# JOYSTICK.net
KiCad netlist of a schematic drawn in EAGLE
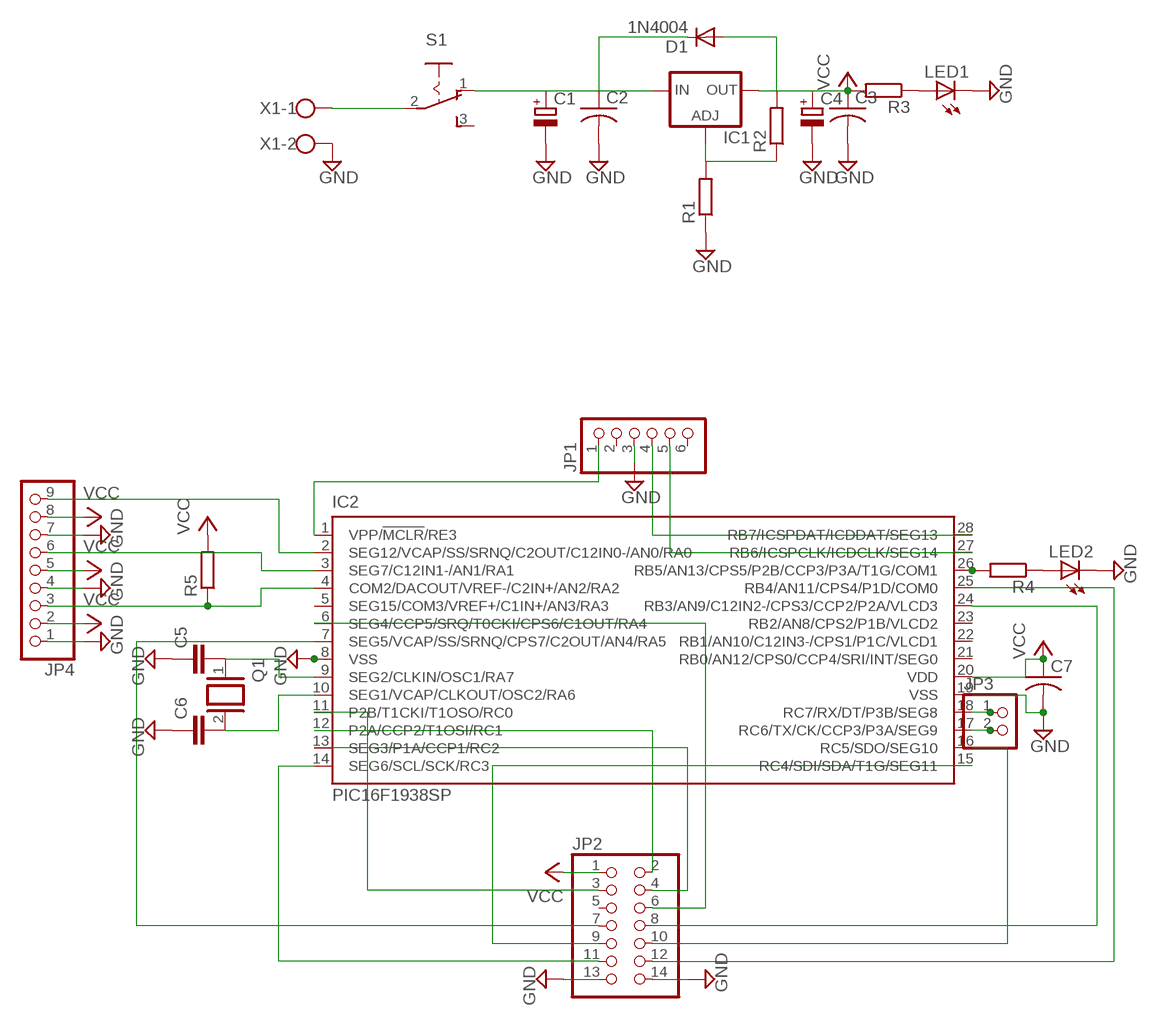
[diagram p0: schematic, sheet 1]

(export (version "E")
  (design (tool "Eeschema 10.0.6"))
  (components
    (comp (ref "C1")
      (value "CPOL-EUE3.5-8")
      (footprint "eagle-import:E3,5-8")
      (libsource (lib "eagle-import") (part "CPOL-EUE3.5-8"))
    )
    (comp (ref "C2")
      (value "C-US050-030X075")
      (footprint "eagle-import:C050-030X075")
      (libsource (lib "eagle-import") (part "C-US050-030X075"))
    )
    (comp (ref "C3")
      (value "C-US050-030X075")
      (footprint "eagle-import:C050-030X075")
      (libsource (lib "eagle-import") (part "C-US050-030X075"))
    )
    (comp (ref "C4")
      (value "CPOL-EUE3.5-8")
      (footprint "eagle-import:E3,5-8")
      (libsource (lib "eagle-import") (part "CPOL-EUE3.5-8"))
    )
    (comp (ref "C5")
      (value "C-EU025-025X050")
      (footprint "eagle-import:C025-025X050")
      (libsource (lib "eagle-import") (part "C-EU025-025X050"))
    )
    (comp (ref "C6")
      (value "C-EU025-025X050")
      (footprint "eagle-import:C025-025X050")
      (libsource (lib "eagle-import") (part "C-EU025-025X050"))
    )
    (comp (ref "C7")
      (value "C-US050-030X075")
      (footprint "eagle-import:C050-030X075")
      (libsource (lib "eagle-import") (part "C-US050-030X075"))
    )
    (comp (ref "D1")
      (value "1N4004")
      (footprint "eagle-import:DO41-10")
      (libsource (lib "eagle-import") (part "1N4004"))
    )
    (comp (ref "IC1")
      (value "LM317TS")
      (footprint "eagle-import:317TS")
      (libsource (lib "eagle-import") (part "LM317TS"))
    )
    (comp (ref "IC2")
      (value "PIC16F1938SP")
      (footprint "eagle-import:DIL28-3")
      (fields (field (name "MPN") "PIC16F1938-I/SP"))
      (libsource (lib "eagle-import") (part "PIC16F19SP38"))
    )
    (comp (ref "JP1")
      (value "PINHD-1X6")
      (footprint "eagle-import:1X06")
      (libsource (lib "eagle-import") (part "PINHD-1X6"))
    )
    (comp (ref "JP2")
      (value "PINHD-2X7")
      (footprint "eagle-import:2X07")
      (libsource (lib "eagle-import") (part "PINHD-2X7"))
    )
    (comp (ref "JP3")
      (value "PINHD-1X2")
      (footprint "eagle-import:1X02")
      (libsource (lib "eagle-import") (part "PINHD-1X2"))
    )
    (comp (ref "JP4")
      (value "PINHD-1X9")
      (footprint "eagle-import:1X09")
      (libsource (lib "eagle-import") (part "PINHD-1X9"))
    )
    (comp (ref "LED1")
      (value "LED5MM")
      (footprint "eagle-import:LED5MM")
      (libsource (lib "eagle-import") (part "LED5MM"))
    )
    (comp (ref "LED2")
      (value "LED5MM")
      (footprint "eagle-import:LED5MM")
      (libsource (lib "eagle-import") (part "LED5MM"))
    )
    (comp (ref "Q1")
      (value "XTAL/S")
      (footprint "eagle-import:QS")
      (libsource (lib "eagle-import") (part "XTAL/S"))
    )
    (comp (ref "R1")
      (value "R-EU_0207/10")
      (footprint "eagle-import:0207_10")
      (libsource (lib "eagle-import") (part "R-EU_0207/10"))
    )
    (comp (ref "R2")
      (value "R-EU_0207/10")
      (footprint "eagle-import:0207_10")
      (libsource (lib "eagle-import") (part "R-EU_0207/10"))
    )
    (comp (ref "R3")
      (value "R-EU_0207/10")
      (footprint "eagle-import:0207_10")
      (libsource (lib "eagle-import") (part "R-EU_0207/10"))
    )
    (comp (ref "R4")
      (value "R-EU_0207/10")
      (footprint "eagle-import:0207_10")
      (libsource (lib "eagle-import") (part "R-EU_0207/10"))
    )
    (comp (ref "R5")
      (value "R-EU_0207/10")
      (footprint "eagle-import:0207_10")
      (libsource (lib "eagle-import") (part "R-EU_0207/10"))
    )
    (comp (ref "S1")
      (value "255SB")
      (footprint "eagle-import:255SB")
      (libsource (lib "eagle-import") (part "255SB"))
    )
    (comp (ref "X1")
      (value "W237-102")
      (footprint "eagle-import:W237-102")
      (fields (field (name "MPN") "237-102"))
      (libsource (lib "eagle-import") (part "W237-102"))
    )
  )
  (nets
    (net (code "1") (name "GND") (class "Default")
      (node (ref "C1") (pin "-") (pinfunction "-_-") (pintype "passive"))
      (node (ref "C2") (pin "2") (pinfunction "2_2") (pintype "passive"))
      (node (ref "C3") (pin "2") (pinfunction "2_2") (pintype "passive"))
      (node (ref "C4") (pin "-") (pinfunction "-_-") (pintype "passive"))
      (node (ref "C5") (pin "1") (pinfunction "1_1") (pintype "passive"))
      (node (ref "C6") (pin "1") (pinfunction "1_1") (pintype "passive"))
      (node (ref "C7") (pin "2") (pinfunction "2_2") (pintype "passive"))
      (node (ref "IC2") (pin "19") (pinfunction "VSS_19") (pintype "power_in"))
      (node (ref "IC2") (pin "8") (pinfunction "VSS_8") (pintype "power_in"))
      (node (ref "JP1") (pin "3") (pinfunction "3_3") (pintype "passive"))
      (node (ref "JP2") (pin "13") (pinfunction "13_13") (pintype "passive"))
      (node (ref "JP2") (pin "14") (pinfunction "14_14") (pintype "passive"))
      (node (ref "JP4") (pin "1") (pinfunction "1_1") (pintype "passive"))
      (node (ref "JP4") (pin "4") (pinfunction "4_4") (pintype "passive"))
      (node (ref "JP4") (pin "7") (pinfunction "7_7") (pintype "passive"))
      (node (ref "LED1") (pin "K") (pinfunction "C_K") (pintype "passive"))
      (node (ref "LED2") (pin "K") (pinfunction "C_K") (pintype "passive"))
      (node (ref "R1") (pin "1") (pinfunction "1_1") (pintype "passive"))
      (node (ref "X1") (pin "2") (pinfunction "KL_2") (pintype "passive"))
    )
    (net (code "2") (name "Net-(IC1-ADJ)") (class "Default")
      (node (ref "IC1") (pin "1") (pinfunction "ADJ_1") (pintype "input"))
      (node (ref "R1") (pin "2") (pinfunction "2_2") (pintype "passive"))
      (node (ref "R2") (pin "1") (pinfunction "1_1") (pintype "passive"))
    )
    (net (code "3") (name "Net-(IC1-IN)") (class "Default")
      (node (ref "C1") (pin "+") (pinfunction "+_+") (pintype "passive"))
      (node (ref "C2") (pin "1") (pinfunction "1_1") (pintype "passive"))
      (node (ref "D1") (pin "C") (pinfunction "C_C") (pintype "passive"))
      (node (ref "IC1") (pin "3") (pinfunction "IN_3") (pintype "input"))
      (node (ref "S1") (pin "1") (pinfunction "O_1") (pintype "passive"))
    )
    (net (code "4") (name "Net-(IC2-COM2{slash}DACOUT{slash}VREF-{slash}C2IN+{slash}AN2{slash}RA2)") (class "Default")
      (node (ref "IC2") (pin "4") (pinfunction "COM2/DACOUT/VREF-/C2IN+/AN2/RA2_4") (pintype "bidirectional"))
      (node (ref "JP4") (pin "3") (pinfunction "3_3") (pintype "passive"))
      (node (ref "R5") (pin "1") (pinfunction "1_1") (pintype "passive"))
    )
    (net (code "5") (name "Net-(IC2-P2A{slash}CCP2{slash}T1OSI{slash}RC1)") (class "Default")
      (node (ref "IC2") (pin "12") (pinfunction "P2A/CCP2/T1OSI/RC1_12") (pintype "bidirectional"))
      (node (ref "JP2") (pin "2") (pinfunction "2_2") (pintype "passive"))
    )
    (net (code "6") (name "Net-(IC2-P2B{slash}T1CKI{slash}T1OSO{slash}RC0)") (class "Default")
      (node (ref "IC2") (pin "11") (pinfunction "P2B/T1CKI/T1OSO/RC0_11") (pintype "bidirectional"))
      (node (ref "JP2") (pin "3") (pinfunction "3_3") (pintype "passive"))
    )
    (net (code "7") (name "Net-(IC2-RB3{slash}AN9{slash}C12IN2-{slash}CPS3{slash}CCP2{slash}P2A{slash}VLCD3)") (class "Default")
      (node (ref "IC2") (pin "24") (pinfunction "RB3/AN9/C12IN2-/CPS3/CCP2/P2A/VLCD3_24") (pintype "bidirectional"))
      (node (ref "JP2") (pin "8") (pinfunction "8_8") (pintype "passive"))
    )
    (net (code "8") (name "Net-(IC2-RB4{slash}AN11{slash}CPS4{slash}P1D{slash}COM0)") (class "Default")
      (node (ref "IC2") (pin "25") (pinfunction "RB4/AN11/CPS4/P1D/COM0_25") (pintype "bidirectional"))
      (node (ref "JP2") (pin "12") (pinfunction "12_12") (pintype "passive"))
    )
    (net (code "9") (name "Net-(IC2-RB5{slash}AN13{slash}CPS5{slash}P2B{slash}CCP3{slash}P3A{slash}T1G{slash}COM1)") (class "Default")
      (node (ref "IC2") (pin "26") (pinfunction "RB5/AN13/CPS5/P2B/CCP3/P3A/T1G/COM1_26") (pintype "bidirectional"))
      (node (ref "R4") (pin "2") (pinfunction "2_2") (pintype "passive"))
    )
    (net (code "10") (name "Net-(IC2-RB6{slash}ICSPCLK{slash}ICDCLK{slash}SEG14)") (class "Default")
      (node (ref "IC2") (pin "27") (pinfunction "RB6/ICSPCLK/ICDCLK/SEG14_27") (pintype "bidirectional"))
      (node (ref "JP1") (pin "5") (pinfunction "5_5") (pintype "passive"))
    )
    (net (code "11") (name "Net-(IC2-RB7{slash}ICSPDAT{slash}ICDDAT{slash}SEG13)") (class "Default")
      (node (ref "IC2") (pin "28") (pinfunction "RB7/ICSPDAT/ICDDAT/SEG13_28") (pintype "bidirectional"))
      (node (ref "JP1") (pin "4") (pinfunction "4_4") (pintype "passive"))
    )
    (net (code "12") (name "Net-(IC2-RC4{slash}SDI{slash}SDA{slash}T1G{slash}SEG11)") (class "Default")
      (node (ref "IC2") (pin "15") (pinfunction "RC4/SDI/SDA/T1G/SEG11_15") (pintype "bidirectional"))
      (node (ref "JP2") (pin "9") (pinfunction "9_9") (pintype "passive"))
    )
    (net (code "13") (name "Net-(IC2-RC5{slash}SDO{slash}SEG10)") (class "Default")
      (node (ref "IC2") (pin "16") (pinfunction "RC5/SDO/SEG10_16") (pintype "bidirectional"))
      (node (ref "JP2") (pin "10") (pinfunction "10_10") (pintype "passive"))
    )
    (net (code "14") (name "Net-(IC2-RC6{slash}TX{slash}CK{slash}CCP3{slash}P3A{slash}SEG9)") (class "Default")
      (node (ref "IC2") (pin "17") (pinfunction "RC6/TX/CK/CCP3/P3A/SEG9_17") (pintype "bidirectional"))
      (node (ref "JP3") (pin "2") (pinfunction "2_2") (pintype "passive"))
    )
    (net (code "15") (name "Net-(IC2-RC7{slash}RX{slash}DT{slash}P3B{slash}SEG8)") (class "Default")
      (node (ref "IC2") (pin "18") (pinfunction "RC7/RX/DT/P3B/SEG8_18") (pintype "bidirectional"))
      (node (ref "JP3") (pin "1") (pinfunction "1_1") (pintype "passive"))
    )
    (net (code "16") (name "Net-(IC2-SEG1{slash}VCAP{slash}CLKOUT{slash}OSC2{slash}RA6)") (class "Default")
      (node (ref "C6") (pin "2") (pinfunction "2_2") (pintype "passive"))
      (node (ref "IC2") (pin "10") (pinfunction "SEG1/VCAP/CLKOUT/OSC2/RA6_10") (pintype "bidirectional"))
      (node (ref "Q1") (pin "2") (pinfunction "2_2") (pintype "passive"))
    )
    (net (code "17") (name "Net-(IC2-SEG2{slash}CLKIN{slash}OSC1{slash}RA7)") (class "Default")
      (node (ref "C5") (pin "2") (pinfunction "2_2") (pintype "passive"))
      (node (ref "IC2") (pin "9") (pinfunction "SEG2/CLKIN/OSC1/RA7_9") (pintype "bidirectional"))
      (node (ref "Q1") (pin "1") (pinfunction "1_1") (pintype "passive"))
    )
    (net (code "18") (name "Net-(IC2-SEG3{slash}P1A{slash}CCP1{slash}RC2)") (class "Default")
      (node (ref "IC2") (pin "13") (pinfunction "SEG3/P1A/CCP1/RC2_13") (pintype "bidirectional"))
      (node (ref "JP2") (pin "4") (pinfunction "4_4") (pintype "passive"))
    )
    (net (code "19") (name "Net-(IC2-SEG4{slash}CCP5{slash}SRQ{slash}T0CKI{slash}CPS6{slash}C1OUT{slash}RA4)") (class "Default")
      (node (ref "IC2") (pin "6") (pinfunction "SEG4/CCP5/SRQ/T0CKI/CPS6/C1OUT/RA4_6") (pintype "bidirectional"))
      (node (ref "JP2") (pin "6") (pinfunction "6_6") (pintype "passive"))
    )
    (net (code "20") (name "Net-(IC2-SEG5{slash}VCAP{slash}SS{slash}SRNQ{slash}CPS7{slash}C2OUT{slash}AN4{slash}RA5)") (class "Default")
      (node (ref "IC2") (pin "7") (pinfunction "SEG5/VCAP/SS/SRNQ/CPS7/C2OUT/AN4/RA5_7") (pintype "bidirectional"))
      (node (ref "JP2") (pin "7") (pinfunction "7_7") (pintype "passive"))
    )
    (net (code "21") (name "Net-(IC2-SEG6{slash}SCL{slash}SCK{slash}RC3)") (class "Default")
      (node (ref "IC2") (pin "14") (pinfunction "SEG6/SCL/SCK/RC3_14") (pintype "bidirectional"))
      (node (ref "JP2") (pin "11") (pinfunction "11_11") (pintype "passive"))
    )
    (net (code "22") (name "Net-(IC2-SEG7{slash}C12IN1-{slash}AN1{slash}RA1)") (class "Default")
      (node (ref "IC2") (pin "3") (pinfunction "SEG7/C12IN1-/AN1/RA1_3") (pintype "bidirectional"))
      (node (ref "JP4") (pin "6") (pinfunction "6_6") (pintype "passive"))
    )
    (net (code "23") (name "Net-(IC2-SEG12{slash}VCAP{slash}SS{slash}SRNQ{slash}C2OUT{slash}C12IN0-{slash}AN0{slash}RA0)") (class "Default")
      (node (ref "IC2") (pin "2") (pinfunction "SEG12/VCAP/SS/SRNQ/C2OUT/C12IN0-/AN0/RA0_2") (pintype "bidirectional"))
      (node (ref "JP4") (pin "9") (pinfunction "9_9") (pintype "passive"))
    )
    (net (code "24") (name "Net-(IC2-VPP{slash}~{MCLR}{slash}RE3)") (class "Default")
      (node (ref "IC2") (pin "1") (pinfunction "VPP/~{MCLR}/RE3_1") (pintype "input"))
      (node (ref "JP1") (pin "1") (pinfunction "1_1") (pintype "passive"))
    )
    (net (code "25") (name "Net-(LED1-PadA)") (class "Default")
      (node (ref "LED1") (pin "A") (pinfunction "A_A") (pintype "passive"))
      (node (ref "R3") (pin "1") (pinfunction "1_1") (pintype "passive"))
    )
    (net (code "26") (name "Net-(LED2-PadA)") (class "Default")
      (node (ref "LED2") (pin "A") (pinfunction "A_A") (pintype "passive"))
      (node (ref "R4") (pin "1") (pinfunction "1_1") (pintype "passive"))
    )
    (net (code "27") (name "Net-(S1-P)") (class "Default")
      (node (ref "S1") (pin "2") (pinfunction "P_2") (pintype "passive"))
      (node (ref "X1") (pin "1") (pinfunction "KL_1") (pintype "passive"))
    )
    (net (code "28") (name "VCC") (class "Default")
      (node (ref "C3") (pin "1") (pinfunction "1_1") (pintype "passive"))
      (node (ref "C4") (pin "+") (pinfunction "+_+") (pintype "passive"))
      (node (ref "C7") (pin "1") (pinfunction "1_1") (pintype "passive"))
      (node (ref "D1") (pin "A") (pinfunction "A_A") (pintype "passive"))
      (node (ref "IC1") (pin "2") (pinfunction "OUT_2") (pintype "passive"))
      (node (ref "IC2") (pin "20") (pinfunction "VDD_20") (pintype "power_in"))
      (node (ref "JP2") (pin "1") (pinfunction "1_1") (pintype "passive"))
      (node (ref "JP4") (pin "2") (pinfunction "2_2") (pintype "passive"))
      (node (ref "JP4") (pin "5") (pinfunction "5_5") (pintype "passive"))
      (node (ref "JP4") (pin "8") (pinfunction "8_8") (pintype "passive"))
      (node (ref "R2") (pin "2") (pinfunction "2_2") (pintype "passive"))
      (node (ref "R3") (pin "2") (pinfunction "2_2") (pintype "passive"))
      (node (ref "R5") (pin "2") (pinfunction "2_2") (pintype "passive"))
    )
    (net (code "29") (name "unconnected-(IC2-RB0{slash}AN12{slash}CPS0{slash}CCP4{slash}SRI{slash}INT{slash}SEG0-Pad21)") (class "Default")
      (node (ref "IC2") (pin "21") (pinfunction "RB0/AN12/CPS0/CCP4/SRI/INT/SEG0_21") (pintype "bidirectional"))
    )
    (net (code "30") (name "unconnected-(IC2-RB1{slash}AN10{slash}C12IN3-{slash}CPS1{slash}P1C{slash}VLCD1-Pad22)") (class "Default")
      (node (ref "IC2") (pin "22") (pinfunction "RB1/AN10/C12IN3-/CPS1/P1C/VLCD1_22") (pintype "bidirectional"))
    )
    (net (code "31") (name "unconnected-(IC2-RB2{slash}AN8{slash}CPS2{slash}P1B{slash}VLCD2-Pad23)") (class "Default")
      (node (ref "IC2") (pin "23") (pinfunction "RB2/AN8/CPS2/P1B/VLCD2_23") (pintype "bidirectional"))
    )
    (net (code "32") (name "unconnected-(IC2-SEG15{slash}COM3{slash}VREF+{slash}C1IN+{slash}AN3{slash}RA3-Pad5)") (class "Default")
      (node (ref "IC2") (pin "5") (pinfunction "SEG15/COM3/VREF+/C1IN+/AN3/RA3_5") (pintype "bidirectional"))
    )
    (net (code "33") (name "unconnected-(JP1-Pad2)") (class "Default")
      (node (ref "JP1") (pin "2") (pinfunction "2_2") (pintype "passive"))
    )
    (net (code "34") (name "unconnected-(JP1-Pad6)") (class "Default")
      (node (ref "JP1") (pin "6") (pinfunction "6_6") (pintype "passive"))
    )
    (net (code "35") (name "unconnected-(JP2-Pad5)") (class "Default")
      (node (ref "JP2") (pin "5") (pinfunction "5_5") (pintype "passive"))
    )
    (net (code "36") (name "unconnected-(S1-S-Pad3)") (class "Default")
      (node (ref "S1") (pin "3") (pinfunction "S_3") (pintype "passive"))
    )
  )
)
